# grizzly_bear.net
KiCad netlist of a schematic drawn in EAGLE
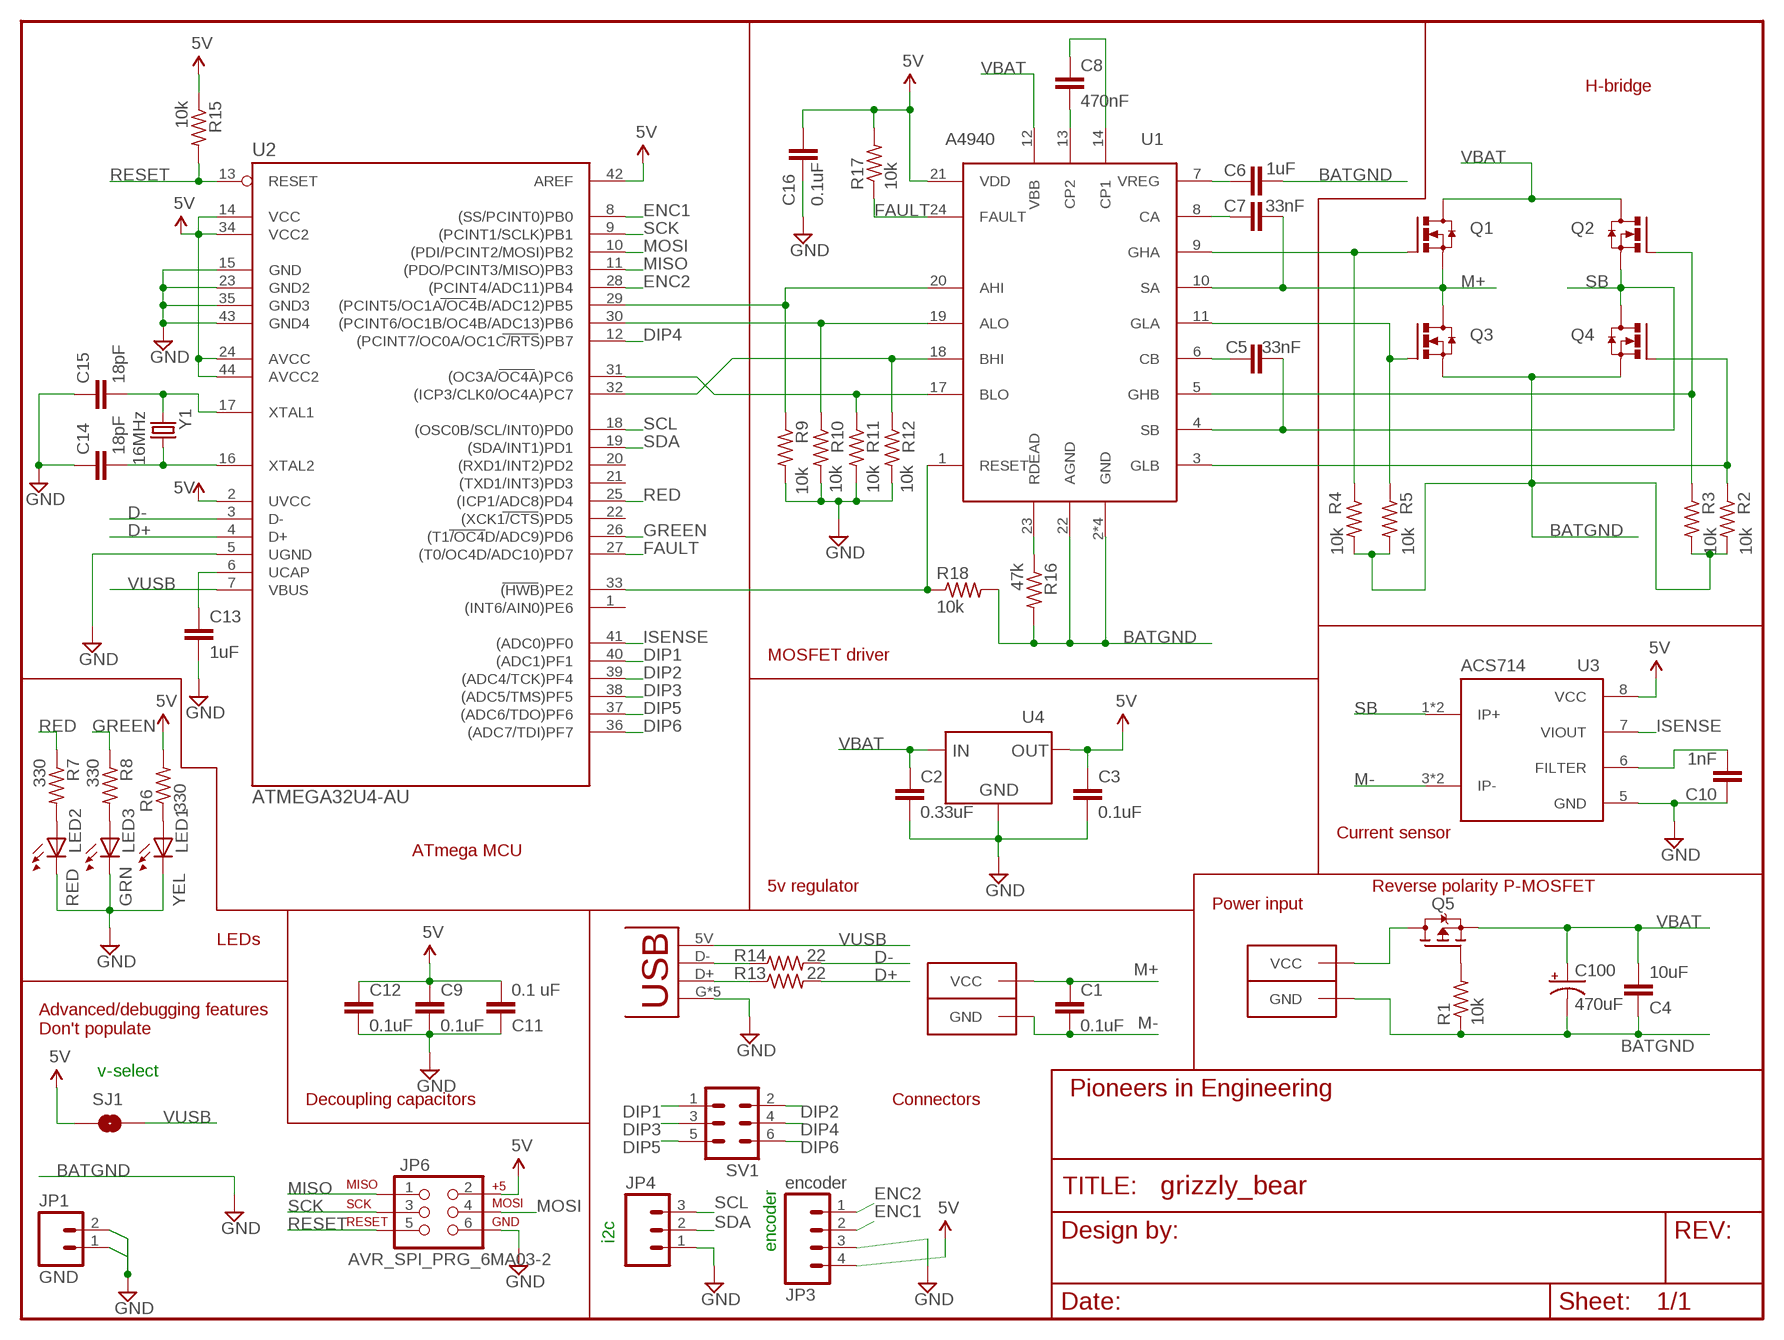
[diagram p0: schematic, sheet 1]

(export (version "E")
  (design (tool "Eeschema 10.0.6"))
  (components
    (comp (ref "C1")
      (value "0.1uF")
      (footprint "eagle-import:0603-CAP")
      (libsource (lib "eagle-import") (part "CAP0603-CAP"))
    )
    (comp (ref "C2")
      (value "0.33uF")
      (footprint "eagle-import:0603-CAP")
      (libsource (lib "eagle-import") (part "CAP0603-CAP"))
    )
    (comp (ref "C3")
      (value "0.1uF")
      (footprint "eagle-import:0603-CAP")
      (libsource (lib "eagle-import") (part "CAP0603-CAP"))
    )
    (comp (ref "C4")
      (value "10uF")
      (footprint "eagle-import:0603-CAP")
      (libsource (lib "eagle-import") (part "CAP0603-CAP"))
    )
    (comp (ref "C5")
      (value "33nF")
      (footprint "eagle-import:0603-CAP")
      (libsource (lib "eagle-import") (part "CAP0603-CAP"))
    )
    (comp (ref "C6")
      (value "1uF")
      (footprint "eagle-import:0603-CAP")
      (libsource (lib "eagle-import") (part "CAP0603-CAP"))
    )
    (comp (ref "C7")
      (value "33nF")
      (footprint "eagle-import:0603-CAP")
      (libsource (lib "eagle-import") (part "CAP0603-CAP"))
    )
    (comp (ref "C8")
      (value "470nF")
      (footprint "eagle-import:0603-CAP")
      (libsource (lib "eagle-import") (part "CAP0603-CAP"))
    )
    (comp (ref "C9")
      (value "0.1uF")
      (footprint "eagle-import:0603-CAP")
      (libsource (lib "eagle-import") (part "CAP0603-CAP"))
    )
    (comp (ref "C10")
      (value "1nF")
      (footprint "eagle-import:0603-CAP")
      (libsource (lib "eagle-import") (part "CAP0603-CAP"))
    )
    (comp (ref "C11")
      (value "0.1 uF")
      (footprint "eagle-import:0603-CAP")
      (libsource (lib "eagle-import") (part "CAP0603-CAP"))
    )
    (comp (ref "C12")
      (value "0.1uF")
      (footprint "eagle-import:0603-CAP")
      (libsource (lib "eagle-import") (part "CAP0603-CAP"))
    )
    (comp (ref "C13")
      (value "1uF")
      (footprint "eagle-import:0603-CAP")
      (libsource (lib "eagle-import") (part "CAP0603-CAP"))
    )
    (comp (ref "C14")
      (value "18pF")
      (footprint "eagle-import:0603-CAP")
      (libsource (lib "eagle-import") (part "CAP0603-CAP"))
    )
    (comp (ref "C15")
      (value "18pF")
      (footprint "eagle-import:0603-CAP")
      (libsource (lib "eagle-import") (part "CAP0603-CAP"))
    )
    (comp (ref "C16")
      (value "0.1uF")
      (footprint "eagle-import:0603-CAP")
      (libsource (lib "eagle-import") (part "CAP0603-CAP"))
    )
    (comp (ref "C100")
      (value "470uF")
      (footprint "eagle-import:PANASONIC_G")
      (libsource (lib "eagle-import") (part "CAP_POLG"))
    )
    (comp (ref "JP1")
      (value "GND")
      (footprint "eagle-import:1X02")
      (libsource (lib "eagle-import") (part "M02PTH"))
    )
    (comp (ref "JP3")
      (value "encoder")
      (footprint "eagle-import:1X04-MTA")
      (fields (field (name "PARTNUMBER") "A1922-ND"))
      (libsource (lib "eagle-import") (part "M041X04-MTA"))
    )
    (comp (ref "JP4")
      (value "M031X03-MTA")
      (footprint "eagle-import:1X03-MTA")
      (fields (field (name "PARTNUMBER") "A19470-ND"))
      (libsource (lib "eagle-import") (part "M031X03-MTA"))
    )
    (comp (ref "JP6")
      (value "AVR_SPI_PRG_6MA03-2")
      (footprint "eagle-import:MA03-2")
      (libsource (lib "eagle-import") (part "AVR_SPI_PRG_6MA03-2"))
    )
    (comp (ref "LED1")
      (value "YEL")
      (footprint "eagle-import:LED-0805")
      (libsource (lib "eagle-import") (part "LED0805"))
    )
    (comp (ref "LED2")
      (value "RED")
      (footprint "eagle-import:LED-0805")
      (libsource (lib "eagle-import") (part "LED0805"))
    )
    (comp (ref "LED3")
      (value "GRN")
      (footprint "eagle-import:LED-0805")
      (libsource (lib "eagle-import") (part "LED0805"))
    )
    (comp (ref "Q1")
      (value "N-CHANNEL-MOSFET")
      (footprint "eagle-import:SOT669")
      (libsource (lib "eagle-import") (part "N-CHANNEL-MOSFET"))
    )
    (comp (ref "Q2")
      (value "N-CHANNEL-MOSFET")
      (footprint "eagle-import:SOT669")
      (libsource (lib "eagle-import") (part "N-CHANNEL-MOSFET"))
    )
    (comp (ref "Q3")
      (value "N-CHANNEL-MOSFET")
      (footprint "eagle-import:SOT669")
      (libsource (lib "eagle-import") (part "N-CHANNEL-MOSFET"))
    )
    (comp (ref "Q4")
      (value "N-CHANNEL-MOSFET")
      (footprint "eagle-import:SOT669")
      (libsource (lib "eagle-import") (part "N-CHANNEL-MOSFET"))
    )
    (comp (ref "Q5")
      (value "IPD90P03P4L")
      (footprint "eagle-import:TO252")
      (libsource (lib "eagle-import") (part "P-CHANNEL-MOSFETTO252"))
    )
    (comp (ref "R1")
      (value "10k")
      (footprint "eagle-import:R0603")
      (libsource (lib "eagle-import") (part "R-US_R0603"))
    )
    (comp (ref "R2")
      (value "10k")
      (footprint "eagle-import:R0603")
      (libsource (lib "eagle-import") (part "R-US_R0603"))
    )
    (comp (ref "R3")
      (value "10k")
      (footprint "eagle-import:R0603")
      (libsource (lib "eagle-import") (part "R-US_R0603"))
    )
    (comp (ref "R4")
      (value "10k")
      (footprint "eagle-import:R0603")
      (libsource (lib "eagle-import") (part "R-US_R0603"))
    )
    (comp (ref "R5")
      (value "10k")
      (footprint "eagle-import:R0603")
      (libsource (lib "eagle-import") (part "R-US_R0603"))
    )
    (comp (ref "R6")
      (value "330")
      (footprint "eagle-import:R0603")
      (libsource (lib "eagle-import") (part "R-US_R0603"))
    )
    (comp (ref "R7")
      (value "330")
      (footprint "eagle-import:R0603")
      (libsource (lib "eagle-import") (part "R-US_R0603"))
    )
    (comp (ref "R8")
      (value "330")
      (footprint "eagle-import:R0603")
      (libsource (lib "eagle-import") (part "R-US_R0603"))
    )
    (comp (ref "R9")
      (value "10k")
      (footprint "eagle-import:R0603")
      (libsource (lib "eagle-import") (part "R-US_R0603"))
    )
    (comp (ref "R10")
      (value "10k")
      (footprint "eagle-import:R0603")
      (libsource (lib "eagle-import") (part "R-US_R0603"))
    )
    (comp (ref "R11")
      (value "10k")
      (footprint "eagle-import:R0603")
      (libsource (lib "eagle-import") (part "R-US_R0603"))
    )
    (comp (ref "R12")
      (value "10k")
      (footprint "eagle-import:R0603")
      (libsource (lib "eagle-import") (part "R-US_R0603"))
    )
    (comp (ref "R13")
      (value "22")
      (footprint "eagle-import:R0603")
      (libsource (lib "eagle-import") (part "R-US_R0603"))
    )
    (comp (ref "R14")
      (value "22")
      (footprint "eagle-import:R0603")
      (libsource (lib "eagle-import") (part "R-US_R0603"))
    )
    (comp (ref "R15")
      (value "10k")
      (footprint "eagle-import:R0603")
      (libsource (lib "eagle-import") (part "R-US_R0603"))
    )
    (comp (ref "R16")
      (value "47k")
      (footprint "eagle-import:R0603")
      (libsource (lib "eagle-import") (part "R-US_R0603"))
    )
    (comp (ref "R17")
      (value "10k")
      (footprint "eagle-import:R0603")
      (libsource (lib "eagle-import") (part "R-US_R0603"))
    )
    (comp (ref "R18")
      (value "10k")
      (footprint "eagle-import:R0603")
      (libsource (lib "eagle-import") (part "R-US_R0603"))
    )
    (comp (ref "SJ1")
      (value "SOLDERJUMPERNO")
      (footprint "eagle-import:SJ_2S-NO")
      (libsource (lib "eagle-import") (part "SOLDERJUMPERNO"))
    )
    (comp (ref "SV1")
      (value "MA03-2")
      (footprint "eagle-import:MA03-2")
      (libsource (lib "eagle-import") (part "MA03-2"))
    )
    (comp (ref "U$2")
      (value "USB-M26FTR")
      (footprint "eagle-import:USB-M26FTR")
      (libsource (lib "eagle-import") (part "USB-M26FTR"))
    )
    (comp (ref "U$18")
      (value "ANDERSONVERTICAL")
      (footprint "eagle-import:ANDERSON_VERTICAL")
      (fields (field (name "PARTNUMBER") "1377G3"))
      (libsource (lib "eagle-import") (part "ANDERSONVERTICAL"))
    )
    (comp (ref "U$19")
      (value "ANDERSONVERTICAL")
      (footprint "eagle-import:ANDERSON_VERTICAL")
      (fields (field (name "PARTNUMBER") "1377G3"))
      (libsource (lib "eagle-import") (part "ANDERSONVERTICAL"))
    )
    (comp (ref "U1")
      (value "A4940")
      (footprint "eagle-import:24-PIN_TSSOP")
      (libsource (lib "eagle-import") (part "A4940"))
    )
    (comp (ref "U2")
      (value "ATMEGA32U4-AU")
      (footprint "eagle-import:TQFP44")
      (libsource (lib "eagle-import") (part "ATMEGA32U4-AU"))
    )
    (comp (ref "U3")
      (value "ACS714")
      (footprint "eagle-import:8-PIN_SOIC")
      (libsource (lib "eagle-import") (part "ACS714"))
    )
    (comp (ref "U4")
      (value "UA78L00")
      (footprint "eagle-import:SOT-89-3")
      (libsource (lib "eagle-import") (part "UA78L00"))
    )
    (comp (ref "Y1")
      (value "16MHz")
      (footprint "eagle-import:HC49UP")
      (libsource (lib "eagle-import") (part "CRYSTALSMD"))
    )
  )
  (nets
    (net (code "1") (name "/D+") (class "Default")
      (node (ref "R13") (pin "2") (pinfunction "2_2") (pintype "passive"))
      (node (ref "U2") (pin "4") (pinfunction "D+_4") (pintype "bidirectional"))
    )
    (net (code "2") (name "/D-") (class "Default")
      (node (ref "R14") (pin "2") (pinfunction "2_2") (pintype "passive"))
      (node (ref "U2") (pin "3") (pinfunction "D-_3") (pintype "bidirectional"))
    )
    (net (code "3") (name "/DIP1") (class "Default")
      (node (ref "SV1") (pin "1") (pinfunction "1_1") (pintype "passive"))
      (node (ref "U2") (pin "40") (pinfunction "(ADC1)PF1_40") (pintype "bidirectional"))
    )
    (net (code "4") (name "/DIP2") (class "Default")
      (node (ref "SV1") (pin "2") (pinfunction "2_2") (pintype "passive"))
      (node (ref "U2") (pin "39") (pinfunction "(ADC4/TCK)PF4_39") (pintype "bidirectional"))
    )
    (net (code "5") (name "/DIP3") (class "Default")
      (node (ref "SV1") (pin "3") (pinfunction "3_3") (pintype "passive"))
      (node (ref "U2") (pin "38") (pinfunction "(ADC5/TMS)PF5_38") (pintype "bidirectional"))
    )
    (net (code "6") (name "/DIP4") (class "Default")
      (node (ref "SV1") (pin "4") (pinfunction "4_4") (pintype "passive"))
      (node (ref "U2") (pin "12") (pinfunction "(PCINT7/OC0A/OC1C/RTS)PB7_12") (pintype "bidirectional"))
    )
    (net (code "7") (name "/DIP5") (class "Default")
      (node (ref "SV1") (pin "5") (pinfunction "5_5") (pintype "passive"))
      (node (ref "U2") (pin "37") (pinfunction "(ADC6/TDO)PF6_37") (pintype "bidirectional"))
    )
    (net (code "8") (name "/DIP6") (class "Default")
      (node (ref "SV1") (pin "6") (pinfunction "6_6") (pintype "passive"))
      (node (ref "U2") (pin "36") (pinfunction "(ADC7/TDI)PF7_36") (pintype "bidirectional"))
    )
    (net (code "9") (name "/ENC1") (class "Default")
      (node (ref "JP3") (pin "2") (pinfunction "2_2") (pintype "passive"))
      (node (ref "U2") (pin "8") (pinfunction "(SS/PCINT0)PB0_8") (pintype "bidirectional"))
    )
    (net (code "10") (name "/ENC2") (class "Default")
      (node (ref "JP3") (pin "1") (pinfunction "1_1") (pintype "passive"))
      (node (ref "U2") (pin "28") (pinfunction "(PCINT4/ADC11)PB4_28") (pintype "bidirectional"))
    )
    (net (code "11") (name "/FAULT") (class "Default")
      (node (ref "R17") (pin "1") (pinfunction "1_1") (pintype "passive"))
      (node (ref "U1") (pin "24") (pinfunction "FAULT_24") (pintype "bidirectional"))
      (node (ref "U2") (pin "27") (pinfunction "(T0/OC4D/ADC10)PD7_27") (pintype "bidirectional"))
    )
    (net (code "12") (name "/GREEN") (class "Default")
      (node (ref "R8") (pin "1") (pinfunction "1_1") (pintype "passive"))
      (node (ref "U2") (pin "26") (pinfunction "(T1/OC4D/ADC9)PD6_26") (pintype "bidirectional"))
    )
    (net (code "13") (name "/ISENSE") (class "Default")
      (node (ref "U2") (pin "41") (pinfunction "(ADC0)PF0_41") (pintype "bidirectional"))
      (node (ref "U3") (pin "7") (pinfunction "VIOUT_7") (pintype "bidirectional"))
    )
    (net (code "14") (name "/M+") (class "Default")
      (node (ref "C1") (pin "1") (pinfunction "1_1") (pintype "passive"))
      (node (ref "C7") (pin "2") (pinfunction "2_2") (pintype "passive"))
      (node (ref "Q1") (pin "1") (pinfunction "S_1") (pintype "passive"))
      (node (ref "Q1") (pin "2") (pinfunction "S_2") (pintype "passive"))
      (node (ref "Q1") (pin "3") (pinfunction "S_3") (pintype "passive"))
      (node (ref "Q3") (pin "MB") (pinfunction "D_MB") (pintype "passive"))
      (node (ref "U$19") (pin "PIN2") (pinfunction "VCC_PIN2") (pintype "bidirectional"))
      (node (ref "U1") (pin "10") (pinfunction "SA_10") (pintype "bidirectional"))
    )
    (net (code "15") (name "/M-") (class "Default")
      (node (ref "C1") (pin "2") (pinfunction "2_2") (pintype "passive"))
      (node (ref "U$19") (pin "PIN1") (pinfunction "GND_PIN1") (pintype "bidirectional"))
      (node (ref "U3") (pin "3") (pinfunction "IP-_3") (pintype "bidirectional"))
      (node (ref "U3") (pin "4") (pinfunction "IP-_4") (pintype "bidirectional"))
    )
    (net (code "16") (name "/MISO") (class "Default")
      (node (ref "JP6") (pin "1") (pinfunction "1_1") (pintype "passive"))
      (node (ref "U2") (pin "11") (pinfunction "(PDO/PCINT3/MISO)PB3_11") (pintype "bidirectional"))
    )
    (net (code "17") (name "/MOSI") (class "Default")
      (node (ref "JP6") (pin "4") (pinfunction "4_4") (pintype "passive"))
      (node (ref "U2") (pin "10") (pinfunction "(PDI/PCINT2/MOSI)PB2_10") (pintype "bidirectional"))
    )
    (net (code "18") (name "/RED") (class "Default")
      (node (ref "R7") (pin "1") (pinfunction "1_1") (pintype "passive"))
      (node (ref "U2") (pin "25") (pinfunction "(ICP1/ADC8)PD4_25") (pintype "bidirectional"))
    )
    (net (code "19") (name "/RESET") (class "Default")
      (node (ref "JP6") (pin "5") (pinfunction "5_5") (pintype "passive"))
      (node (ref "R15") (pin "2") (pinfunction "2_2") (pintype "passive"))
      (node (ref "U2") (pin "13") (pinfunction "RESET_13") (pintype "bidirectional"))
    )
    (net (code "20") (name "/SB") (class "Default")
      (node (ref "C5") (pin "1") (pinfunction "1_1") (pintype "passive"))
      (node (ref "Q2") (pin "1") (pinfunction "S_1") (pintype "passive"))
      (node (ref "Q2") (pin "2") (pinfunction "S_2") (pintype "passive"))
      (node (ref "Q2") (pin "3") (pinfunction "S_3") (pintype "passive"))
      (node (ref "Q4") (pin "MB") (pinfunction "D_MB") (pintype "passive"))
      (node (ref "U1") (pin "4") (pinfunction "SB_4") (pintype "bidirectional"))
      (node (ref "U3") (pin "1") (pinfunction "IP+_1") (pintype "bidirectional"))
      (node (ref "U3") (pin "2") (pinfunction "IP+_2") (pintype "bidirectional"))
    )
    (net (code "21") (name "/SCK") (class "Default")
      (node (ref "JP6") (pin "3") (pinfunction "3_3") (pintype "passive"))
      (node (ref "U2") (pin "9") (pinfunction "(PCINT1/SCLK)PB1_9") (pintype "bidirectional"))
    )
    (net (code "22") (name "/SCL") (class "Default")
      (node (ref "JP4") (pin "3") (pinfunction "3_3") (pintype "passive"))
      (node (ref "U2") (pin "18") (pinfunction "(OSC0B/SCL/INT0)PD0_18") (pintype "bidirectional"))
    )
    (net (code "23") (name "/SDA") (class "Default")
      (node (ref "JP4") (pin "2") (pinfunction "2_2") (pintype "passive"))
      (node (ref "U2") (pin "19") (pinfunction "(SDA/INT1)PD1_19") (pintype "bidirectional"))
    )
    (net (code "24") (name "/VBAT") (class "Default")
      (node (ref "C100") (pin "+") (pinfunction "+_+") (pintype "passive"))
      (node (ref "C2") (pin "1") (pinfunction "1_1") (pintype "passive"))
      (node (ref "C4") (pin "2") (pinfunction "2_2") (pintype "passive"))
      (node (ref "Q1") (pin "MB") (pinfunction "D_MB") (pintype "passive"))
      (node (ref "Q2") (pin "MB") (pinfunction "D_MB") (pintype "passive"))
      (node (ref "Q5") (pin "2") (pinfunction "S_2") (pintype "passive"))
      (node (ref "U1") (pin "12") (pinfunction "VBB_12") (pintype "bidirectional"))
      (node (ref "U4") (pin "INPUT") (pinfunction "IN_INPUT") (pintype "bidirectional"))
    )
    (net (code "25") (name "/VUSB") (class "Default")
      (node (ref "SJ1") (pin "2") (pinfunction "2_2") (pintype "passive"))
      (node (ref "U$2") (pin "5V") (pinfunction "5V_5V") (pintype "bidirectional"))
      (node (ref "U2") (pin "7") (pinfunction "VBUS_7") (pintype "bidirectional"))
    )
    (net (code "26") (name "5V") (class "Default")
      (node (ref "C11") (pin "2") (pinfunction "2_2") (pintype "passive"))
      (node (ref "C12") (pin "1") (pinfunction "1_1") (pintype "passive"))
      (node (ref "C16") (pin "1") (pinfunction "1_1") (pintype "passive"))
      (node (ref "C3") (pin "1") (pinfunction "1_1") (pintype "passive"))
      (node (ref "C9") (pin "1") (pinfunction "1_1") (pintype "passive"))
      (node (ref "JP3") (pin "4") (pinfunction "4_4") (pintype "passive"))
      (node (ref "JP6") (pin "2") (pinfunction "2_2") (pintype "passive"))
      (node (ref "R15") (pin "1") (pinfunction "1_1") (pintype "passive"))
      (node (ref "R17") (pin "2") (pinfunction "2_2") (pintype "passive"))
      (node (ref "R6") (pin "2") (pinfunction "2_2") (pintype "passive"))
      (node (ref "SJ1") (pin "1") (pinfunction "1_1") (pintype "passive"))
      (node (ref "U1") (pin "21") (pinfunction "VDD_21") (pintype "bidirectional"))
      (node (ref "U2") (pin "14") (pinfunction "VCC_14") (pintype "bidirectional"))
      (node (ref "U2") (pin "2") (pinfunction "UVCC_2") (pintype "bidirectional"))
      (node (ref "U2") (pin "24") (pinfunction "AVCC_24") (pintype "bidirectional"))
      (node (ref "U2") (pin "34") (pinfunction "VCC2_34") (pintype "bidirectional"))
      (node (ref "U2") (pin "42") (pinfunction "AREF_42") (pintype "bidirectional"))
      (node (ref "U2") (pin "44") (pinfunction "AVCC2_44") (pintype "bidirectional"))
      (node (ref "U3") (pin "8") (pinfunction "VCC_8") (pintype "bidirectional"))
      (node (ref "U4") (pin "OUTPUT") (pinfunction "OUT_OUTPUT") (pintype "bidirectional"))
    )
    (net (code "27") (name "GND") (class "Default")
      (node (ref "C10") (pin "1") (pinfunction "1_1") (pintype "passive"))
      (node (ref "C100") (pin "-") (pinfunction "-_-") (pintype "passive"))
      (node (ref "C11") (pin "1") (pinfunction "1_1") (pintype "passive"))
      (node (ref "C12") (pin "2") (pinfunction "2_2") (pintype "passive"))
      (node (ref "C13") (pin "2") (pinfunction "2_2") (pintype "passive"))
      (node (ref "C14") (pin "1") (pinfunction "1_1") (pintype "passive"))
      (node (ref "C15") (pin "1") (pinfunction "1_1") (pintype "passive"))
      (node (ref "C16") (pin "2") (pinfunction "2_2") (pintype "passive"))
      (node (ref "C2") (pin "2") (pinfunction "2_2") (pintype "passive"))
      (node (ref "C3") (pin "2") (pinfunction "2_2") (pintype "passive"))
      (node (ref "C4") (pin "1") (pinfunction "1_1") (pintype "passive"))
      (node (ref "C6") (pin "2") (pinfunction "2_2") (pintype "passive"))
      (node (ref "C9") (pin "2") (pinfunction "2_2") (pintype "passive"))
      (node (ref "JP1") (pin "1") (pinfunction "1_1") (pintype "passive"))
      (node (ref "JP1") (pin "2") (pinfunction "2_2") (pintype "passive"))
      (node (ref "JP3") (pin "3") (pinfunction "3_3") (pintype "passive"))
      (node (ref "JP4") (pin "1") (pinfunction "1_1") (pintype "passive"))
      (node (ref "JP6") (pin "6") (pinfunction "6_6") (pintype "passive"))
      (node (ref "LED1") (pin "C") (pinfunction "C_C") (pintype "passive"))
      (node (ref "LED2") (pin "C") (pinfunction "C_C") (pintype "passive"))
      (node (ref "LED3") (pin "C") (pinfunction "C_C") (pintype "passive"))
      (node (ref "Q3") (pin "1") (pinfunction "S_1") (pintype "passive"))
      (node (ref "Q3") (pin "2") (pinfunction "S_2") (pintype "passive"))
      (node (ref "Q3") (pin "3") (pinfunction "S_3") (pintype "passive"))
      (node (ref "Q4") (pin "1") (pinfunction "S_1") (pintype "passive"))
      (node (ref "Q4") (pin "2") (pinfunction "S_2") (pintype "passive"))
      (node (ref "Q4") (pin "3") (pinfunction "S_3") (pintype "passive"))
      (node (ref "R1") (pin "1") (pinfunction "1_1") (pintype "passive"))
      (node (ref "R10") (pin "2") (pinfunction "2_2") (pintype "passive"))
      (node (ref "R11") (pin "2") (pinfunction "2_2") (pintype "passive"))
      (node (ref "R12") (pin "2") (pinfunction "2_2") (pintype "passive"))
      (node (ref "R16") (pin "2") (pinfunction "2_2") (pintype "passive"))
      (node (ref "R18") (pin "2") (pinfunction "2_2") (pintype "passive"))
      (node (ref "R2") (pin "2") (pinfunction "2_2") (pintype "passive"))
      (node (ref "R3") (pin "2") (pinfunction "2_2") (pintype "passive"))
      (node (ref "R4") (pin "2") (pinfunction "2_2") (pintype "passive"))
      (node (ref "R5") (pin "2") (pinfunction "2_2") (pintype "passive"))
      (node (ref "R9") (pin "2") (pinfunction "2_2") (pintype "passive"))
      (node (ref "U$18") (pin "PIN1") (pinfunction "GND_PIN1") (pintype "bidirectional"))
      (node (ref "U$2") (pin "G") (pinfunction "G_G") (pintype "bidirectional"))
      (node (ref "U$2") (pin "S1") (pinfunction "G_S1") (pintype "bidirectional"))
      (node (ref "U$2") (pin "S2") (pinfunction "G_S2") (pintype "bidirectional"))
      (node (ref "U$2") (pin "S3") (pinfunction "G_S3") (pintype "bidirectional"))
      (node (ref "U$2") (pin "S4") (pinfunction "G_S4") (pintype "bidirectional"))
      (node (ref "U1") (pin "15") (pinfunction "GND_15") (pintype "bidirectional"))
      (node (ref "U1") (pin "16") (pinfunction "GND_16") (pintype "bidirectional"))
      (node (ref "U1") (pin "2") (pinfunction "GND_2") (pintype "bidirectional"))
      (node (ref "U1") (pin "22") (pinfunction "AGND_22") (pintype "bidirectional"))
      (node (ref "U1") (pin "PAD") (pinfunction "GND_PAD") (pintype "bidirectional"))
      (node (ref "U2") (pin "15") (pinfunction "GND_15") (pintype "bidirectional"))
      (node (ref "U2") (pin "23") (pinfunction "GND2_23") (pintype "bidirectional"))
      (node (ref "U2") (pin "35") (pinfunction "GND3_35") (pintype "bidirectional"))
      (node (ref "U2") (pin "43") (pinfunction "GND4_43") (pintype "bidirectional"))
      (node (ref "U2") (pin "5") (pinfunction "UGND_5") (pintype "bidirectional"))
      (node (ref "U3") (pin "5") (pinfunction "GND_5") (pintype "bidirectional"))
      (node (ref "U4") (pin "COMMON") (pinfunction "GND_COMMON") (pintype "bidirectional"))
    )
    (net (code "28") (name "Net-(LED1-PadA)") (class "Default")
      (node (ref "LED1") (pin "A") (pinfunction "A_A") (pintype "passive"))
      (node (ref "R6") (pin "1") (pinfunction "1_1") (pintype "passive"))
    )
    (net (code "29") (name "Net-(LED2-PadA)") (class "Default")
      (node (ref "LED2") (pin "A") (pinfunction "A_A") (pintype "passive"))
      (node (ref "R7") (pin "2") (pinfunction "2_2") (pintype "passive"))
    )
    (net (code "30") (name "Net-(LED3-PadA)") (class "Default")
      (node (ref "LED3") (pin "A") (pinfunction "A_A") (pintype "passive"))
      (node (ref "R8") (pin "2") (pinfunction "2_2") (pintype "passive"))
    )
    (net (code "31") (name "Net-(Q1-G)") (class "Default")
      (node (ref "Q1") (pin "4") (pinfunction "G_4") (pintype "passive"))
      (node (ref "R4") (pin "1") (pinfunction "1_1") (pintype "passive"))
      (node (ref "U1") (pin "9") (pinfunction "GHA_9") (pintype "bidirectional"))
    )
    (net (code "32") (name "Net-(Q2-G)") (class "Default")
      (node (ref "Q2") (pin "4") (pinfunction "G_4") (pintype "passive"))
      (node (ref "R3") (pin "1") (pinfunction "1_1") (pintype "passive"))
      (node (ref "U1") (pin "5") (pinfunction "GHB_5") (pintype "bidirectional"))
    )
    (net (code "33") (name "Net-(Q3-G)") (class "Default")
      (node (ref "Q3") (pin "4") (pinfunction "G_4") (pintype "passive"))
      (node (ref "R5") (pin "1") (pinfunction "1_1") (pintype "passive"))
      (node (ref "U1") (pin "11") (pinfunction "GLA_11") (pintype "bidirectional"))
    )
    (net (code "34") (name "Net-(Q4-G)") (class "Default")
      (node (ref "Q4") (pin "4") (pinfunction "G_4") (pintype "passive"))
      (node (ref "R2") (pin "1") (pinfunction "1_1") (pintype "passive"))
      (node (ref "U1") (pin "3") (pinfunction "GLB_3") (pintype "bidirectional"))
    )
    (net (code "35") (name "Net-(Q5-D)") (class "Default")
      (node (ref "Q5") (pin "3") (pinfunction "D_3") (pintype "passive"))
      (node (ref "U$18") (pin "PIN2") (pinfunction "VCC_PIN2") (pintype "bidirectional"))
    )
    (net (code "36") (name "Net-(Q5-G)") (class "Default")
      (node (ref "Q5") (pin "1") (pinfunction "G_1") (pintype "passive"))
      (node (ref "R1") (pin "2") (pinfunction "2_2") (pintype "passive"))
    )
    (net (code "37") (name "Net-(R13-Pad1)") (class "Default")
      (node (ref "R13") (pin "1") (pinfunction "1_1") (pintype "passive"))
      (node (ref "U$2") (pin "D+") (pinfunction "D+_D+") (pintype "bidirectional"))
    )
    (net (code "38") (name "Net-(R14-Pad1)") (class "Default")
      (node (ref "R14") (pin "1") (pinfunction "1_1") (pintype "passive"))
      (node (ref "U$2") (pin "D-") (pinfunction "D-_D-") (pintype "bidirectional"))
    )
    (net (code "39") (name "Net-(U1-AHI)") (class "Default")
      (node (ref "R9") (pin "1") (pinfunction "1_1") (pintype "passive"))
      (node (ref "U1") (pin "20") (pinfunction "AHI_20") (pintype "bidirectional"))
      (node (ref "U2") (pin "29") (pinfunction "(PCINT5/OC1A/OC4B/ADC12)PB5_29") (pintype "bidirectional"))
    )
    (net (code "40") (name "Net-(U1-ALO)") (class "Default")
      (node (ref "R10") (pin "1") (pinfunction "1_1") (pintype "passive"))
      (node (ref "U1") (pin "19") (pinfunction "ALO_19") (pintype "bidirectional"))
      (node (ref "U2") (pin "30") (pinfunction "(PCINT6/OC1B/OC4B/ADC13)PB6_30") (pintype "bidirectional"))
    )
    (net (code "41") (name "Net-(U1-BHI)") (class "Default")
      (node (ref "R12") (pin "1") (pinfunction "1_1") (pintype "passive"))
      (node (ref "U1") (pin "18") (pinfunction "BHI_18") (pintype "bidirectional"))
      (node (ref "U2") (pin "32") (pinfunction "(ICP3/CLK0/OC4A)PC7_32") (pintype "bidirectional"))
    )
    (net (code "42") (name "Net-(U1-BLO)") (class "Default")
      (node (ref "R11") (pin "1") (pinfunction "1_1") (pintype "passive"))
      (node (ref "U1") (pin "17") (pinfunction "BLO_17") (pintype "bidirectional"))
      (node (ref "U2") (pin "31") (pinfunction "(OC3A/OC4A)PC6_31") (pintype "bidirectional"))
    )
    (net (code "43") (name "Net-(U1-CA)") (class "Default")
      (node (ref "C7") (pin "1") (pinfunction "1_1") (pintype "passive"))
      (node (ref "U1") (pin "8") (pinfunction "CA_8") (pintype "bidirectional"))
    )
    (net (code "44") (name "Net-(U1-CB)") (class "Default")
      (node (ref "C5") (pin "2") (pinfunction "2_2") (pintype "passive"))
      (node (ref "U1") (pin "6") (pinfunction "CB_6") (pintype "bidirectional"))
    )
    (net (code "45") (name "Net-(U1-CP1)") (class "Default")
      (node (ref "C8") (pin "1") (pinfunction "1_1") (pintype "passive"))
      (node (ref "U1") (pin "14") (pinfunction "CP1_14") (pintype "bidirectional"))
    )
    (net (code "46") (name "Net-(U1-CP2)") (class "Default")
      (node (ref "C8") (pin "2") (pinfunction "2_2") (pintype "passive"))
      (node (ref "U1") (pin "13") (pinfunction "CP2_13") (pintype "bidirectional"))
    )
    (net (code "47") (name "Net-(U1-RDEAD)") (class "Default")
      (node (ref "R16") (pin "1") (pinfunction "1_1") (pintype "passive"))
      (node (ref "U1") (pin "23") (pinfunction "RDEAD_23") (pintype "bidirectional"))
    )
    (net (code "48") (name "Net-(U1-RESET)") (class "Default")
      (node (ref "R18") (pin "1") (pinfunction "1_1") (pintype "passive"))
      (node (ref "U1") (pin "1") (pinfunction "RESET_1") (pintype "bidirectional"))
      (node (ref "U2") (pin "33") (pinfunction "(HWB)PE2_33") (pintype "bidirectional"))
    )
    (net (code "49") (name "Net-(U1-VREG)") (class "Default")
      (node (ref "C6") (pin "1") (pinfunction "1_1") (pintype "passive"))
      (node (ref "U1") (pin "7") (pinfunction "VREG_7") (pintype "bidirectional"))
    )
    (net (code "50") (name "Net-(U2-UCAP)") (class "Default")
      (node (ref "C13") (pin "1") (pinfunction "1_1") (pintype "passive"))
      (node (ref "U2") (pin "6") (pinfunction "UCAP_6") (pintype "bidirectional"))
    )
    (net (code "51") (name "Net-(U2-XTAL1)") (class "Default")
      (node (ref "C15") (pin "2") (pinfunction "2_2") (pintype "passive"))
      (node (ref "U2") (pin "17") (pinfunction "XTAL1_17") (pintype "bidirectional"))
      (node (ref "Y1") (pin "2") (pinfunction "2_2") (pintype "passive"))
    )
    (net (code "52") (name "Net-(U2-XTAL2)") (class "Default")
      (node (ref "C14") (pin "2") (pinfunction "2_2") (pintype "passive"))
      (node (ref "U2") (pin "16") (pinfunction "XTAL2_16") (pintype "bidirectional"))
      (node (ref "Y1") (pin "1") (pinfunction "1_1") (pintype "passive"))
    )
    (net (code "53") (name "Net-(U3-FILTER)") (class "Default")
      (node (ref "C10") (pin "2") (pinfunction "2_2") (pintype "passive"))
      (node (ref "U3") (pin "6") (pinfunction "FILTER_6") (pintype "bidirectional"))
    )
    (net (code "54") (name "unconnected-(U2-(INT6{slash}AIN0)PE6-Pad1)") (class "Default")
      (node (ref "U2") (pin "1") (pinfunction "(INT6/AIN0)PE6_1") (pintype "bidirectional"))
    )
    (net (code "55") (name "unconnected-(U2-(RXD1{slash}INT2)PD2-Pad20)") (class "Default")
      (node (ref "U2") (pin "20") (pinfunction "(RXD1/INT2)PD2_20") (pintype "bidirectional"))
    )
    (net (code "56") (name "unconnected-(U2-(TXD1{slash}INT3)PD3-Pad21)") (class "Default")
      (node (ref "U2") (pin "21") (pinfunction "(TXD1/INT3)PD3_21") (pintype "bidirectional"))
    )
    (net (code "57") (name "unconnected-(U2-(XCK1{slash}CTS)PD5-Pad22)") (class "Default")
      (node (ref "U2") (pin "22") (pinfunction "(XCK1/CTS)PD5_22") (pintype "bidirectional"))
    )
  )
)
